# CarPower.net
KiCad netlist of a schematic drawn in EAGLE
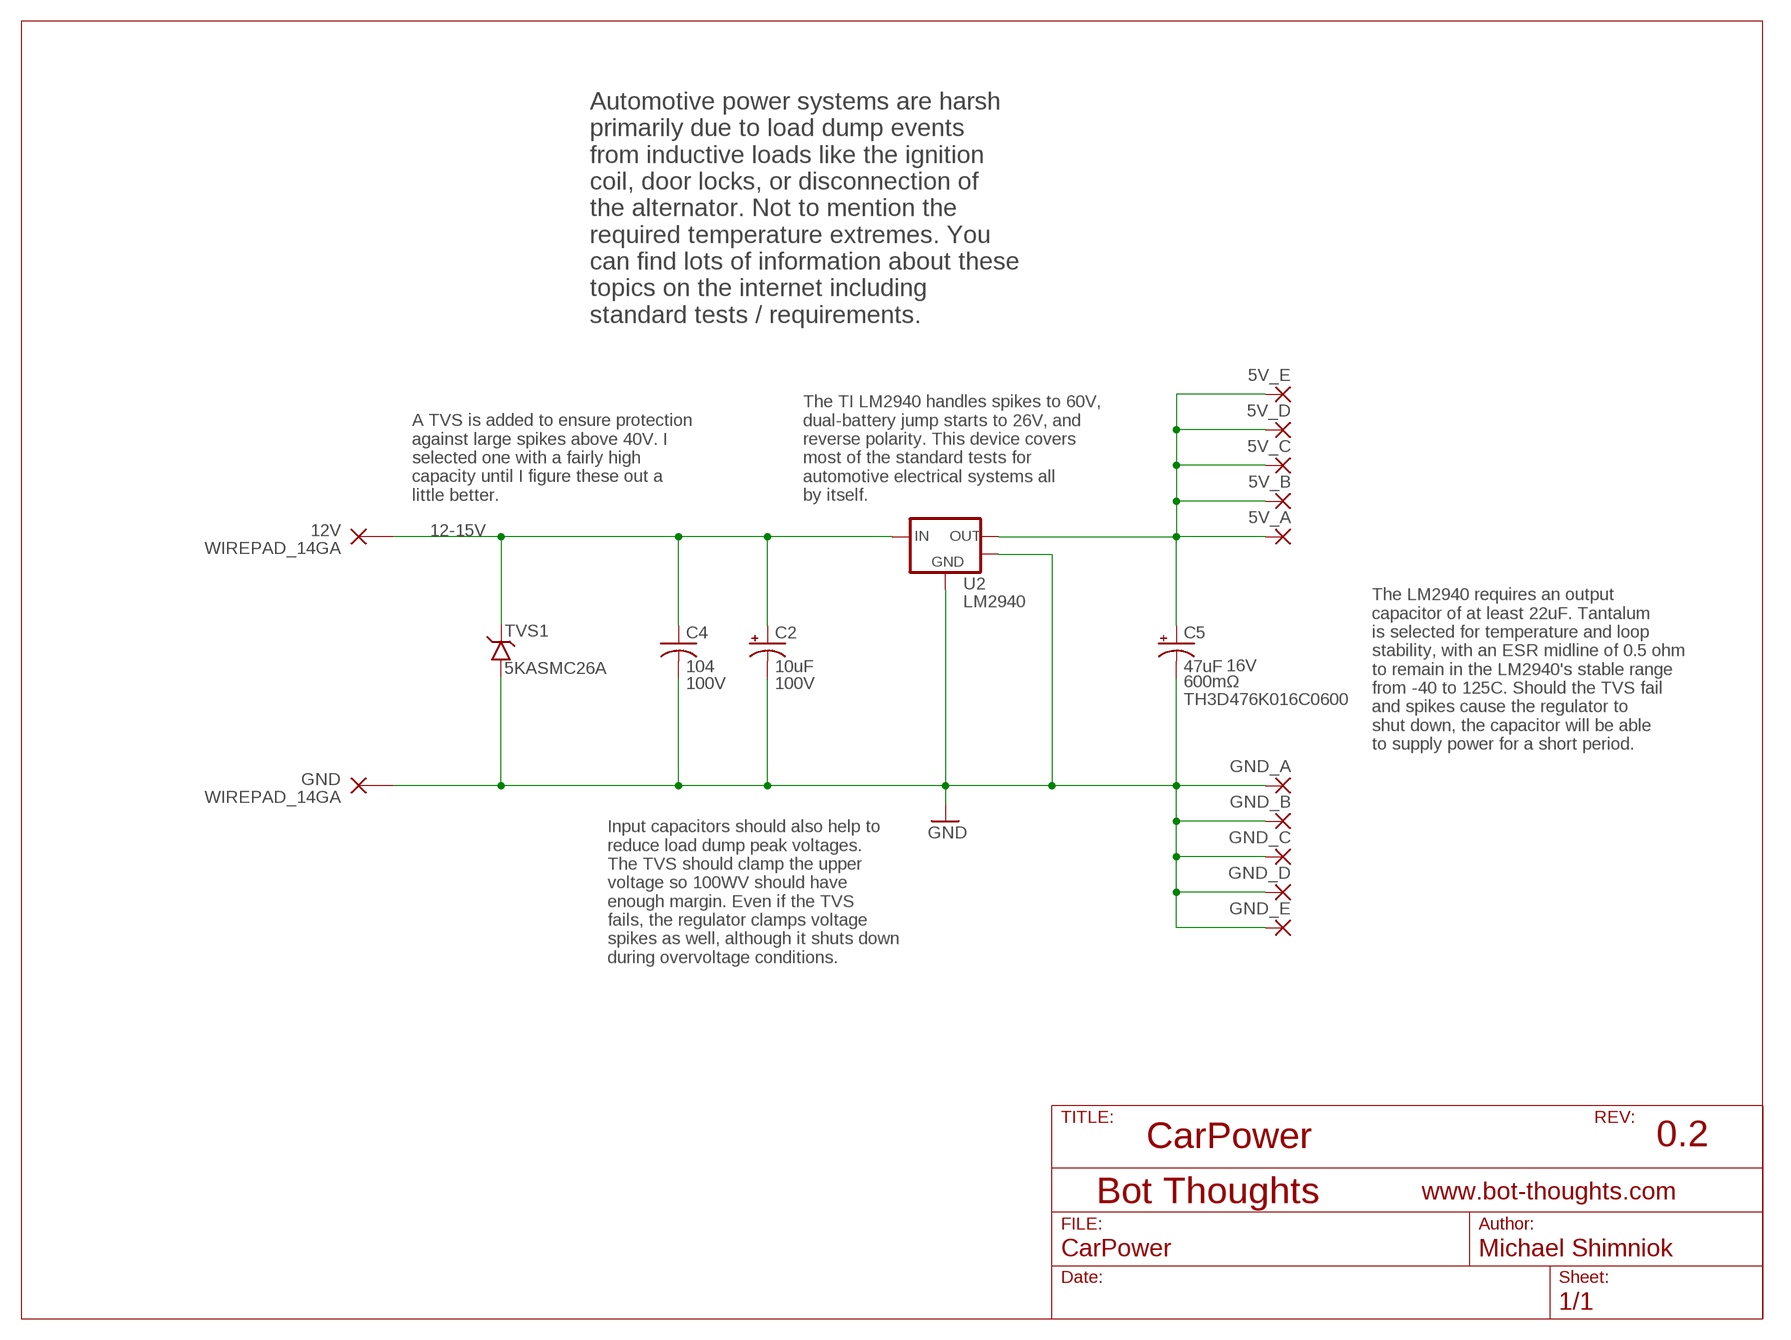
[diagram p0: schematic, sheet 1]

(export (version "E")
  (design (tool "Eeschema 10.0.6"))
  (components
    (comp (ref "5V_A")
      (value "1,6/0,9")
      (footprint "eagle-import:1,6_0,9")
      (libsource (lib "eagle-import") (part "1,6/0,9"))
    )
    (comp (ref "5V_B")
      (value "1,6/0,9")
      (footprint "eagle-import:1,6_0,9")
      (libsource (lib "eagle-import") (part "1,6/0,9"))
    )
    (comp (ref "5V_C")
      (value "1,6/0,9")
      (footprint "eagle-import:1,6_0,9")
      (libsource (lib "eagle-import") (part "1,6/0,9"))
    )
    (comp (ref "5V_D")
      (value "1,6/0,9")
      (footprint "eagle-import:1,6_0,9")
      (libsource (lib "eagle-import") (part "1,6/0,9"))
    )
    (comp (ref "5V_E")
      (value "1,6/0,9")
      (footprint "eagle-import:1,6_0,9")
      (libsource (lib "eagle-import") (part "1,6/0,9"))
    )
    (comp (ref "12V")
      (value "WIREPAD_14GA")
      (footprint "eagle-import:PAD_14GA")
      (libsource (lib "eagle-import") (part "WIREPAD_14GA"))
    )
    (comp (ref "C2")
      (value "10uF")
      (footprint "eagle-import:E3,5-8")
      (fields (field (name "VOLTAGE") "100V"))
      (libsource (lib "eagle-import") (part "CPOL-USE3.5-8"))
    )
    (comp (ref "C4")
      (value "104")
      (footprint "eagle-import:C025-024X044")
      (fields (field (name "VOLTAGE") "100V"))
      (libsource (lib "eagle-import") (part "C-US025-024X044"))
    )
    (comp (ref "C5")
      (value "47uF")
      (footprint "eagle-import:SMC_C")
      (fields
        (field (name "ESR") "600mΩ")
        (field (name "PARTNO") "TH3D476K016C0600")
        (field (name "VOLTAGE") "16V")
      )
      (libsource (lib "eagle-import") (part "CPOL-USSMCC"))
    )
    (comp (ref "GND")
      (value "WIREPAD_14GA")
      (footprint "eagle-import:PAD_14GA")
      (libsource (lib "eagle-import") (part "WIREPAD_14GA"))
    )
    (comp (ref "GND_A")
      (value "1,6/0,9")
      (footprint "eagle-import:1,6_0,9")
      (libsource (lib "eagle-import") (part "1,6/0,9"))
    )
    (comp (ref "GND_B")
      (value "1,6/0,9")
      (footprint "eagle-import:1,6_0,9")
      (libsource (lib "eagle-import") (part "1,6/0,9"))
    )
    (comp (ref "GND_C")
      (value "1,6/0,9")
      (footprint "eagle-import:1,6_0,9")
      (libsource (lib "eagle-import") (part "1,6/0,9"))
    )
    (comp (ref "GND_D")
      (value "1,6/0,9")
      (footprint "eagle-import:1,6_0,9")
      (libsource (lib "eagle-import") (part "1,6/0,9"))
    )
    (comp (ref "GND_E")
      (value "1,6/0,9")
      (footprint "eagle-import:1,6_0,9")
      (libsource (lib "eagle-import") (part "1,6/0,9"))
    )
    (comp (ref "TVS1")
      (value "5KASMC26A")
      (footprint "eagle-import:DO-214AB")
      (libsource (lib "eagle-import") (part "5KASMC"))
    )
    (comp (ref "U2")
      (value "LM2940")
      (footprint "eagle-import:TO263-3")
      (libsource (lib "eagle-import") (part "LM2940KTT"))
    )
  )
  (nets
    (net (code "1") (name "/12-15V") (class "Default")
      (node (ref "12V") (pin "P$1") (pinfunction "P_P$1") (pintype "bidirectional"))
      (node (ref "C2") (pin "+") (pinfunction "+_+") (pintype "passive"))
      (node (ref "C4") (pin "1") (pinfunction "1_1") (pintype "passive"))
      (node (ref "TVS1") (pin "C") (pinfunction "C_C") (pintype "passive"))
      (node (ref "U2") (pin "1") (pinfunction "VIN_1") (pintype "bidirectional"))
    )
    (net (code "2") (name "GND") (class "Default")
      (node (ref "C2") (pin "-") (pinfunction "-_-") (pintype "passive"))
      (node (ref "C4") (pin "2") (pinfunction "2_2") (pintype "passive"))
      (node (ref "C5") (pin "-") (pinfunction "-_-") (pintype "passive"))
      (node (ref "GND") (pin "P$1") (pinfunction "P_P$1") (pintype "bidirectional"))
      (node (ref "GND_A") (pin "1") (pinfunction "P_1") (pintype "passive"))
      (node (ref "GND_B") (pin "1") (pinfunction "P_1") (pintype "passive"))
      (node (ref "GND_C") (pin "1") (pinfunction "P_1") (pintype "passive"))
      (node (ref "GND_D") (pin "1") (pinfunction "P_1") (pintype "passive"))
      (node (ref "GND_E") (pin "1") (pinfunction "P_1") (pintype "passive"))
      (node (ref "TVS1") (pin "A") (pinfunction "A_A") (pintype "passive"))
      (node (ref "U2") (pin "2") (pinfunction "GND_2") (pintype "bidirectional"))
      (node (ref "U2") (pin "4") (pinfunction "TAB_4") (pintype "bidirectional"))
    )
    (net (code "3") (name "Net-(5V_A-P)") (class "Default")
      (node (ref "5V_A") (pin "1") (pinfunction "P_1") (pintype "passive"))
      (node (ref "5V_B") (pin "1") (pinfunction "P_1") (pintype "passive"))
      (node (ref "5V_C") (pin "1") (pinfunction "P_1") (pintype "passive"))
      (node (ref "5V_D") (pin "1") (pinfunction "P_1") (pintype "passive"))
      (node (ref "5V_E") (pin "1") (pinfunction "P_1") (pintype "passive"))
      (node (ref "C5") (pin "+") (pinfunction "+_+") (pintype "passive"))
      (node (ref "U2") (pin "3") (pinfunction "VOUT_3") (pintype "bidirectional"))
    )
  )
)
